# appledore.net
KiCad netlist of a schematic drawn in EasyEDA
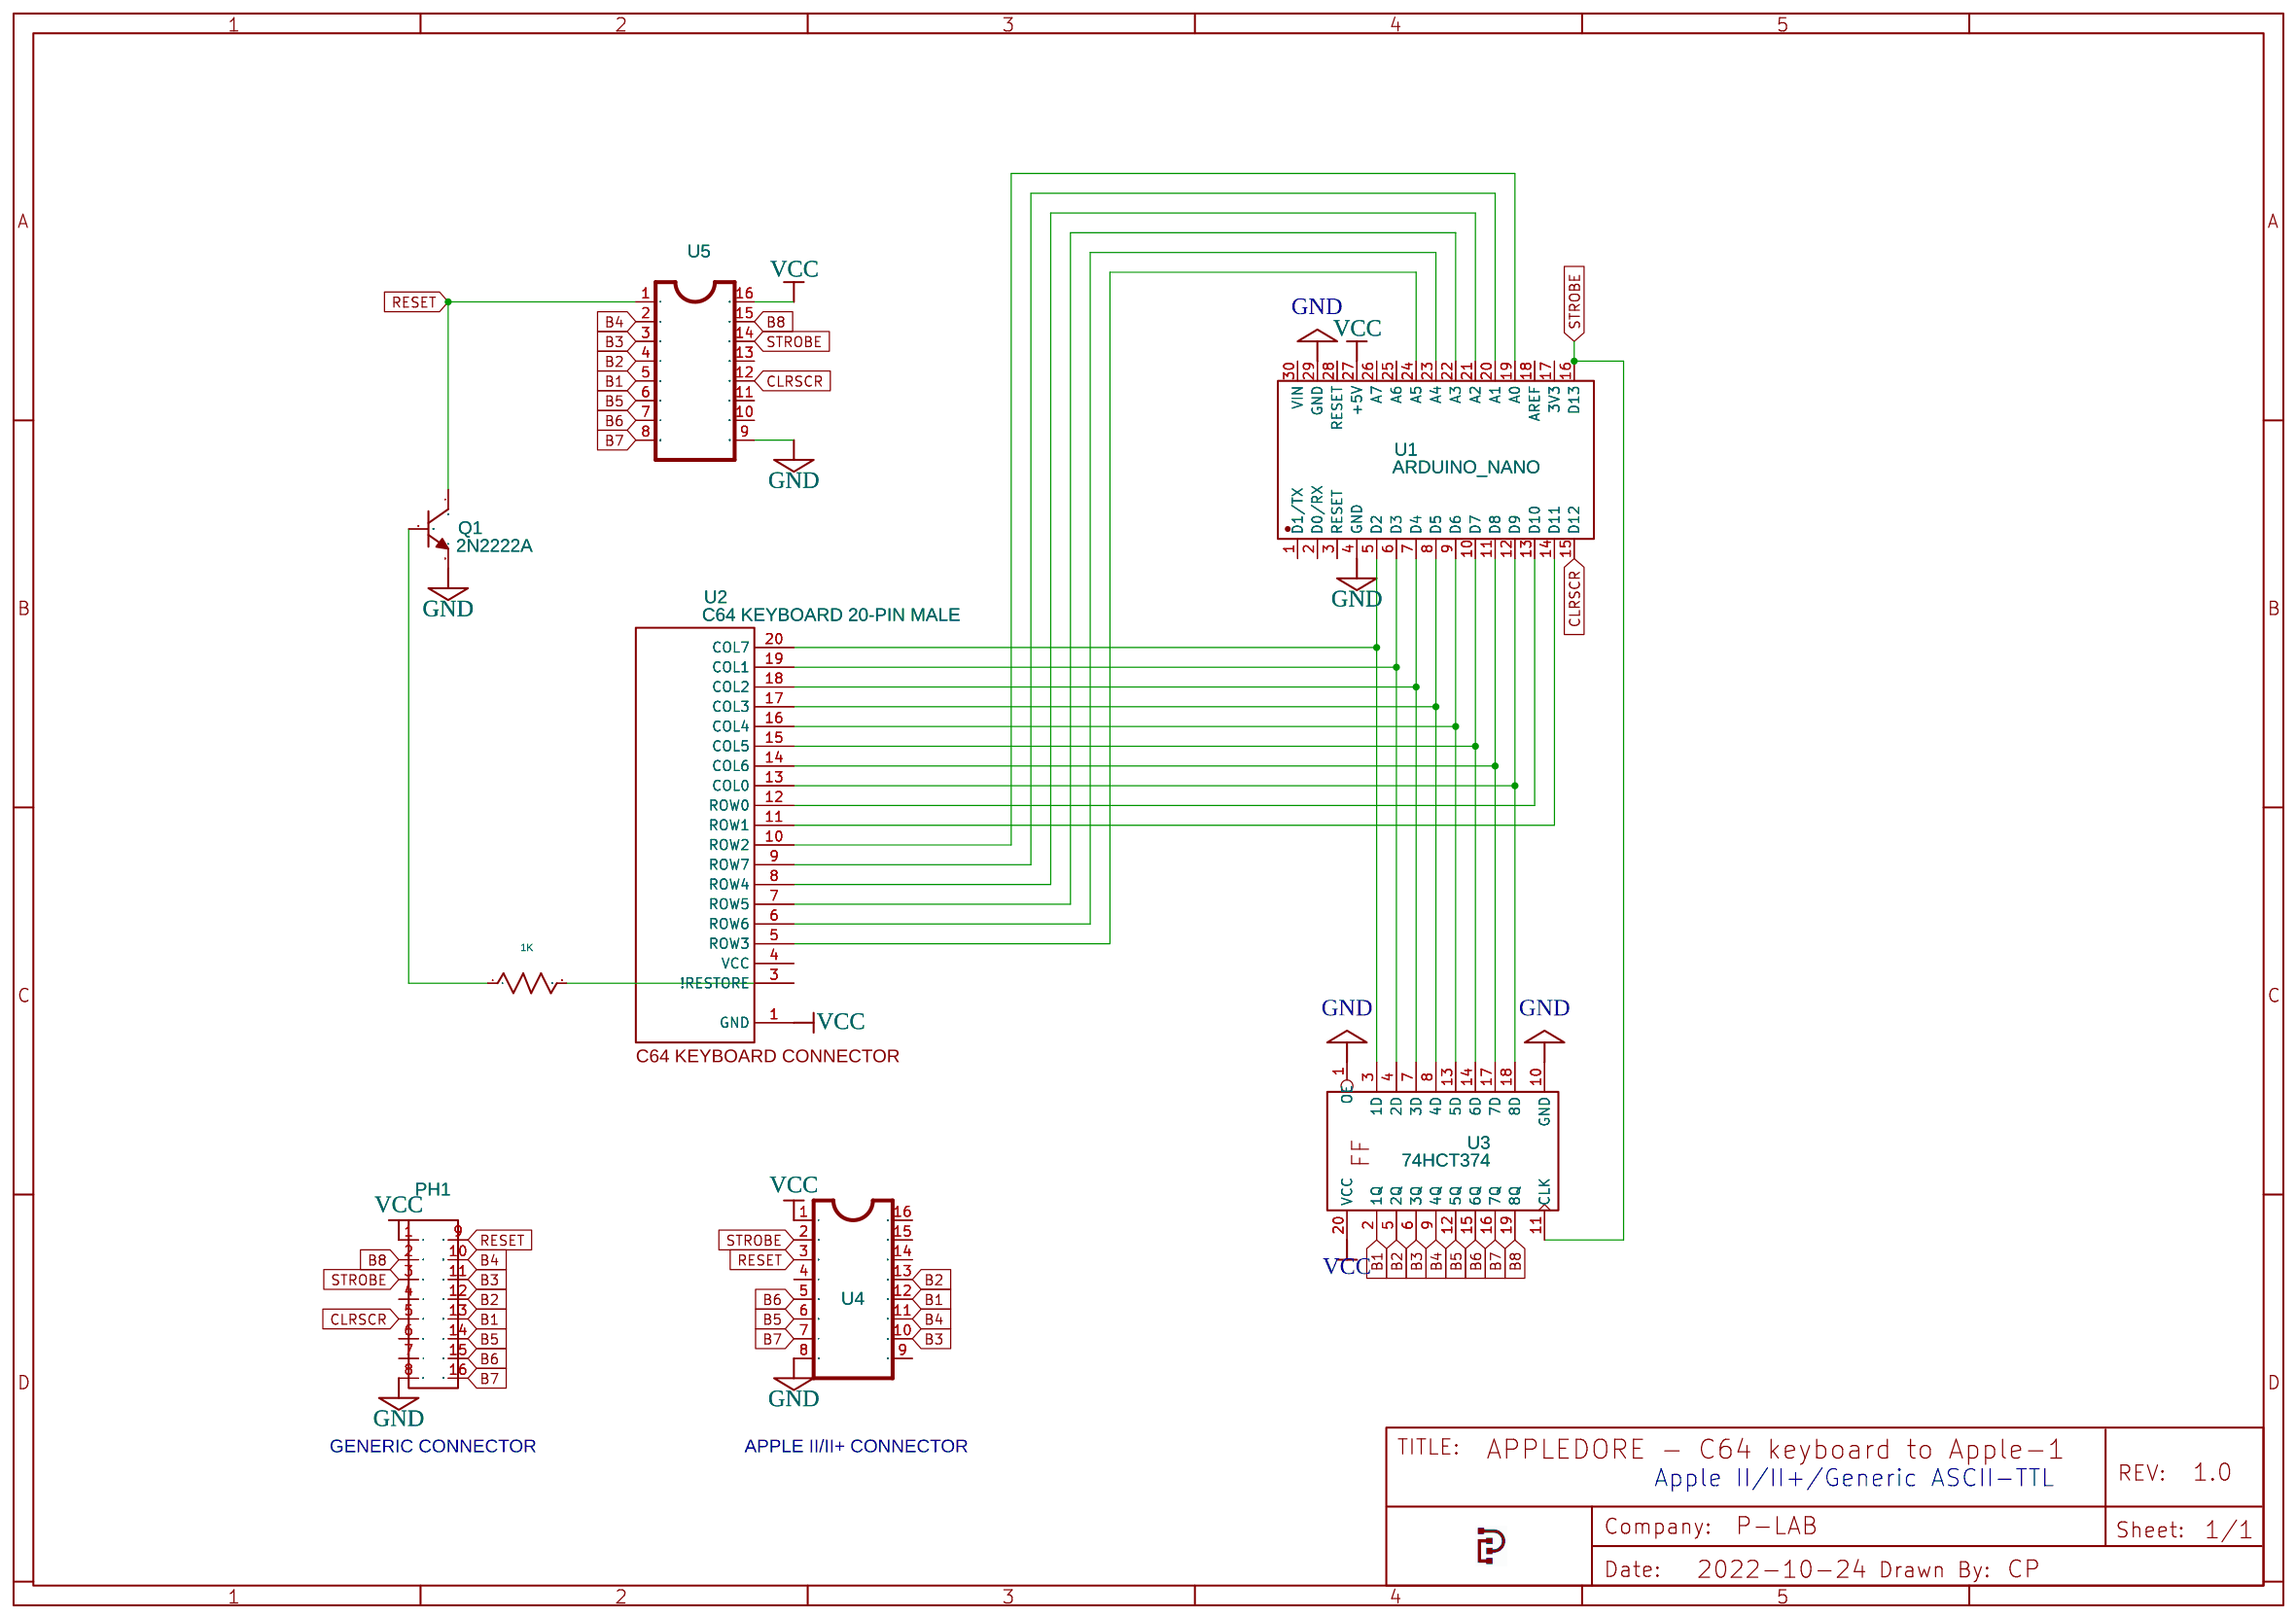
[diagram p0: schematic sheet]

(export (version "E")
  (design (tool "Eeschema 10.0.6"))
  (components
    (comp (ref "1K") (value "1/4W RESISTOR") (libsource (lib "") (part "1/4W RESISTOR")))
    (comp (ref "PH1")
      (value "pinheader08x2")
      (fields (field (name "BOM_Manufacturer Part") "Header 6x1"))
      (libsource (lib "") (part "pinheader08x2"))
    )
    (comp (ref "Q1")
      (value "2N2222A")
      (fields (field (name "BOM_Supplier Part") "C358533"))
      (libsource (lib "") (part "2N2222A"))
    )
    (comp (ref "U1")
      (value "ARDUINO_NANO")
      (fields (field (name "BOM_Supplier Part") "C9900017879"))
      (libsource (lib "") (part "ARDUINO_NANO"))
    )
    (comp (ref "U2")
      (value "C64 KEYBOARD 20-PIN MALE")
      (libsource (lib "") (part "C64 KEYBOARD 20-PIN MALE"))
    )
    (comp (ref "U3") (value "74HCT374") (libsource (lib "") (part "74HCT374")))
    (comp (ref "U4") (value "IC_DIL16-DIP16") (libsource (lib "") (part "IC_DIL16-DIP16")))
    (comp (ref "U5") (value "IC_DIL16-DIP16") (libsource (lib "") (part "IC_DIL16-DIP16")))
  )
  (nets
    (net (code "1") (name "B1") (class "Default")
      (node (ref "PH1") (pin "13") (pinfunction "13_13") (pintype "unspecified"))
      (node (ref "U3") (pin "2") (pinfunction "1Q_2") (pintype "unspecified"))
      (node (ref "U4") (pin "12") (pinfunction "12_12") (pintype "unspecified"))
      (node (ref "U5") (pin "5") (pinfunction "5_5") (pintype "unspecified"))
    )
    (net (code "2") (name "B2") (class "Default")
      (node (ref "PH1") (pin "12") (pinfunction "12_12") (pintype "unspecified"))
      (node (ref "U3") (pin "5") (pinfunction "2Q_5") (pintype "unspecified"))
      (node (ref "U4") (pin "13") (pinfunction "13_13") (pintype "unspecified"))
      (node (ref "U5") (pin "4") (pinfunction "4_4") (pintype "unspecified"))
    )
    (net (code "3") (name "B3") (class "Default")
      (node (ref "PH1") (pin "11") (pinfunction "11_11") (pintype "unspecified"))
      (node (ref "U3") (pin "6") (pinfunction "3Q_6") (pintype "unspecified"))
      (node (ref "U4") (pin "10") (pinfunction "10_10") (pintype "unspecified"))
      (node (ref "U5") (pin "3") (pinfunction "3_3") (pintype "unspecified"))
    )
    (net (code "4") (name "B4") (class "Default")
      (node (ref "PH1") (pin "10") (pinfunction "10_10") (pintype "unspecified"))
      (node (ref "U3") (pin "9") (pinfunction "4Q_9") (pintype "unspecified"))
      (node (ref "U4") (pin "11") (pinfunction "11_11") (pintype "unspecified"))
      (node (ref "U5") (pin "2") (pinfunction "2_2") (pintype "unspecified"))
    )
    (net (code "5") (name "B5") (class "Default")
      (node (ref "PH1") (pin "14") (pinfunction "14_14") (pintype "unspecified"))
      (node (ref "U3") (pin "12") (pinfunction "5Q_12") (pintype "unspecified"))
      (node (ref "U4") (pin "6") (pinfunction "6_6") (pintype "unspecified"))
      (node (ref "U5") (pin "6") (pinfunction "6_6") (pintype "unspecified"))
    )
    (net (code "6") (name "B6") (class "Default")
      (node (ref "PH1") (pin "15") (pinfunction "15_15") (pintype "unspecified"))
      (node (ref "U3") (pin "15") (pinfunction "6Q_15") (pintype "unspecified"))
      (node (ref "U4") (pin "5") (pinfunction "5_5") (pintype "unspecified"))
      (node (ref "U5") (pin "7") (pinfunction "7_7") (pintype "unspecified"))
    )
    (net (code "7") (name "B7") (class "Default")
      (node (ref "PH1") (pin "16") (pinfunction "16_16") (pintype "unspecified"))
      (node (ref "U3") (pin "16") (pinfunction "7Q_16") (pintype "unspecified"))
      (node (ref "U4") (pin "7") (pinfunction "7_7") (pintype "unspecified"))
      (node (ref "U5") (pin "8") (pinfunction "8_8") (pintype "unspecified"))
    )
    (net (code "8") (name "B8") (class "Default")
      (node (ref "PH1") (pin "2") (pinfunction "2_2") (pintype "unspecified"))
      (node (ref "U3") (pin "19") (pinfunction "8Q_19") (pintype "unspecified"))
      (node (ref "U5") (pin "15") (pinfunction "15_15") (pintype "unspecified"))
    )
    (net (code "9") (name "CLRSCR") (class "Default")
      (node (ref "PH1") (pin "5") (pinfunction "5_5") (pintype "unspecified"))
      (node (ref "U1") (pin "15") (pinfunction "D12_15") (pintype "unspecified"))
      (node (ref "U5") (pin "12") (pinfunction "12_12") (pintype "unspecified"))
    )
    (net (code "10") (name "GND") (class "Default")
      (node (ref "PH1") (pin "8") (pinfunction "8_8") (pintype "unspecified"))
      (node (ref "Q1") (pin "3") (pinfunction "E_3") (pintype "unspecified"))
      (node (ref "U1") (pin "29") (pinfunction "GND_29") (pintype "unspecified"))
      (node (ref "U1") (pin "4") (pinfunction "GND_4") (pintype "unspecified"))
      (node (ref "U3") (pin "1") (pinfunction "OE_1") (pintype "unspecified"))
      (node (ref "U3") (pin "10") (pinfunction "GND_10") (pintype "unspecified"))
      (node (ref "U4") (pin "8") (pinfunction "8_8") (pintype "unspecified"))
      (node (ref "U5") (pin "9") (pinfunction "9_9") (pintype "unspecified"))
    )
    (net (code "11") (name "Net-(Q1-B)") (class "Default")
      (node (ref "1K") (pin "1") (pinfunction "1_1") (pintype "unspecified"))
      (node (ref "Q1") (pin "2") (pinfunction "B_2") (pintype "unspecified"))
    )
    (net (code "12") (name "Net-(U1-A0)") (class "Default")
      (node (ref "U1") (pin "19") (pinfunction "A0_19") (pintype "unspecified"))
      (node (ref "U2") (pin "10") (pinfunction "ROW2_10") (pintype "unspecified"))
    )
    (net (code "13") (name "Net-(U1-A1)") (class "Default")
      (node (ref "U1") (pin "20") (pinfunction "A1_20") (pintype "unspecified"))
      (node (ref "U2") (pin "9") (pinfunction "ROW7_9") (pintype "unspecified"))
    )
    (net (code "14") (name "Net-(U1-A2)") (class "Default")
      (node (ref "U1") (pin "21") (pinfunction "A2_21") (pintype "unspecified"))
      (node (ref "U2") (pin "8") (pinfunction "ROW4_8") (pintype "unspecified"))
    )
    (net (code "15") (name "Net-(U1-A3)") (class "Default")
      (node (ref "U1") (pin "22") (pinfunction "A3_22") (pintype "unspecified"))
      (node (ref "U2") (pin "7") (pinfunction "ROW5_7") (pintype "unspecified"))
    )
    (net (code "16") (name "Net-(U1-A4)") (class "Default")
      (node (ref "U1") (pin "23") (pinfunction "A4_23") (pintype "unspecified"))
      (node (ref "U2") (pin "6") (pinfunction "ROW6_6") (pintype "unspecified"))
    )
    (net (code "17") (name "Net-(U1-A5)") (class "Default")
      (node (ref "U1") (pin "24") (pinfunction "A5_24") (pintype "unspecified"))
      (node (ref "U2") (pin "5") (pinfunction "ROW3_5") (pintype "unspecified"))
    )
    (net (code "18") (name "Net-(U1-D2)") (class "Default")
      (node (ref "U1") (pin "5") (pinfunction "D2_5") (pintype "unspecified"))
      (node (ref "U2") (pin "20") (pinfunction "COL7_20") (pintype "unspecified"))
      (node (ref "U3") (pin "3") (pinfunction "1D_3") (pintype "unspecified"))
    )
    (net (code "19") (name "Net-(U1-D3)") (class "Default")
      (node (ref "U1") (pin "6") (pinfunction "D3_6") (pintype "unspecified"))
      (node (ref "U2") (pin "19") (pinfunction "COL1_19") (pintype "unspecified"))
      (node (ref "U3") (pin "4") (pinfunction "2D_4") (pintype "unspecified"))
    )
    (net (code "20") (name "Net-(U1-D4)") (class "Default")
      (node (ref "U1") (pin "7") (pinfunction "D4_7") (pintype "unspecified"))
      (node (ref "U2") (pin "18") (pinfunction "COL2_18") (pintype "unspecified"))
      (node (ref "U3") (pin "7") (pinfunction "3D_7") (pintype "unspecified"))
    )
    (net (code "21") (name "Net-(U1-D5)") (class "Default")
      (node (ref "U1") (pin "8") (pinfunction "D5_8") (pintype "unspecified"))
      (node (ref "U2") (pin "17") (pinfunction "COL3_17") (pintype "unspecified"))
      (node (ref "U3") (pin "8") (pinfunction "4D_8") (pintype "unspecified"))
    )
    (net (code "22") (name "Net-(U1-D6)") (class "Default")
      (node (ref "U1") (pin "9") (pinfunction "D6_9") (pintype "unspecified"))
      (node (ref "U2") (pin "16") (pinfunction "COL4_16") (pintype "unspecified"))
      (node (ref "U3") (pin "13") (pinfunction "5D_13") (pintype "unspecified"))
    )
    (net (code "23") (name "Net-(U1-D7)") (class "Default")
      (node (ref "U1") (pin "10") (pinfunction "D7_10") (pintype "unspecified"))
      (node (ref "U2") (pin "15") (pinfunction "COL5_15") (pintype "unspecified"))
      (node (ref "U3") (pin "14") (pinfunction "6D_14") (pintype "unspecified"))
    )
    (net (code "24") (name "Net-(U1-D8)") (class "Default")
      (node (ref "U1") (pin "11") (pinfunction "D8_11") (pintype "unspecified"))
      (node (ref "U2") (pin "14") (pinfunction "COL6_14") (pintype "unspecified"))
      (node (ref "U3") (pin "17") (pinfunction "7D_17") (pintype "unspecified"))
    )
    (net (code "25") (name "Net-(U1-D9)") (class "Default")
      (node (ref "U1") (pin "12") (pinfunction "D9_12") (pintype "unspecified"))
      (node (ref "U2") (pin "13") (pinfunction "COL0_13") (pintype "unspecified"))
      (node (ref "U3") (pin "18") (pinfunction "8D_18") (pintype "unspecified"))
    )
    (net (code "26") (name "Net-(U1-D10)") (class "Default")
      (node (ref "U1") (pin "13") (pinfunction "D10_13") (pintype "unspecified"))
      (node (ref "U2") (pin "12") (pinfunction "ROW0_12") (pintype "unspecified"))
    )
    (net (code "27") (name "Net-(U1-D11)") (class "Default")
      (node (ref "U1") (pin "14") (pinfunction "D11_14") (pintype "unspecified"))
      (node (ref "U2") (pin "11") (pinfunction "ROW1_11") (pintype "unspecified"))
    )
    (net (code "28") (name "Net-(U2-!RESTORE)") (class "Default")
      (node (ref "1K") (pin "2") (pinfunction "2_2") (pintype "unspecified"))
      (node (ref "U2") (pin "3") (pinfunction "!RESTORE_3") (pintype "unspecified"))
    )
    (net (code "29") (name "RESET") (class "Default")
      (node (ref "PH1") (pin "9") (pinfunction "9_9") (pintype "unspecified"))
      (node (ref "Q1") (pin "1") (pinfunction "C_1") (pintype "unspecified"))
      (node (ref "U4") (pin "3") (pinfunction "3_3") (pintype "unspecified"))
      (node (ref "U5") (pin "1") (pinfunction "1_1") (pintype "unspecified"))
    )
    (net (code "30") (name "STROBE") (class "Default")
      (node (ref "PH1") (pin "3") (pinfunction "3_3") (pintype "unspecified"))
      (node (ref "U1") (pin "16") (pinfunction "D13_16") (pintype "unspecified"))
      (node (ref "U3") (pin "11") (pinfunction "CLK_11") (pintype "unspecified"))
      (node (ref "U4") (pin "2") (pinfunction "2_2") (pintype "unspecified"))
      (node (ref "U5") (pin "14") (pinfunction "14_14") (pintype "unspecified"))
    )
    (net (code "31") (name "VCC") (class "Default")
      (node (ref "PH1") (pin "1") (pinfunction "1_1") (pintype "unspecified"))
      (node (ref "U1") (pin "27") (pinfunction "+5V_27") (pintype "unspecified"))
      (node (ref "U2") (pin "1") (pinfunction "GND_1") (pintype "unspecified"))
      (node (ref "U3") (pin "20") (pinfunction "VCC_20") (pintype "unspecified"))
      (node (ref "U4") (pin "1") (pinfunction "1_1") (pintype "unspecified"))
      (node (ref "U5") (pin "16") (pinfunction "16_16") (pintype "unspecified"))
    )
    (net (code "32") (name "unconnected-(PH1-Pad4)") (class "Default")
      (node (ref "PH1") (pin "4") (pinfunction "4_4") (pintype "unspecified"))
    )
    (net (code "33") (name "unconnected-(PH1-Pad6)") (class "Default")
      (node (ref "PH1") (pin "6") (pinfunction "6_6") (pintype "unspecified"))
    )
    (net (code "34") (name "unconnected-(PH1-Pad7)") (class "Default")
      (node (ref "PH1") (pin "7") (pinfunction "7_7") (pintype "unspecified"))
    )
    (net (code "35") (name "unconnected-(U1-3V3-Pad17)") (class "Default")
      (node (ref "U1") (pin "17") (pinfunction "3V3_17") (pintype "unspecified"))
    )
    (net (code "36") (name "unconnected-(U1-A6-Pad25)") (class "Default")
      (node (ref "U1") (pin "25") (pinfunction "A6_25") (pintype "unspecified"))
    )
    (net (code "37") (name "unconnected-(U1-A7-Pad26)") (class "Default")
      (node (ref "U1") (pin "26") (pinfunction "A7_26") (pintype "unspecified"))
    )
    (net (code "38") (name "unconnected-(U1-AREF-Pad18)") (class "Default")
      (node (ref "U1") (pin "18") (pinfunction "AREF_18") (pintype "unspecified"))
    )
    (net (code "39") (name "unconnected-(U1-D0{slash}RX-Pad2)") (class "Default")
      (node (ref "U1") (pin "2") (pinfunction "D0/RX_2") (pintype "unspecified"))
    )
    (net (code "40") (name "unconnected-(U1-D1{slash}TX-Pad1)") (class "Default")
      (node (ref "U1") (pin "1") (pinfunction "D1/TX_1") (pintype "unspecified"))
    )
    (net (code "41") (name "unconnected-(U1-RESET-Pad3)") (class "Default")
      (node (ref "U1") (pin "3") (pinfunction "RESET_3") (pintype "unspecified"))
    )
    (net (code "42") (name "unconnected-(U1-RESET-Pad28)") (class "Default")
      (node (ref "U1") (pin "28") (pinfunction "RESET_28") (pintype "unspecified"))
    )
    (net (code "43") (name "unconnected-(U1-VIN-Pad30)") (class "Default")
      (node (ref "U1") (pin "30") (pinfunction "VIN_30") (pintype "unspecified"))
    )
    (net (code "44") (name "unconnected-(U2-VCC-Pad4)") (class "Default")
      (node (ref "U2") (pin "4") (pinfunction "VCC_4") (pintype "unspecified"))
    )
    (net (code "45") (name "unconnected-(U4-Pad4)") (class "Default")
      (node (ref "U4") (pin "4") (pinfunction "4_4") (pintype "unspecified"))
    )
    (net (code "46") (name "unconnected-(U4-Pad9)") (class "Default")
      (node (ref "U4") (pin "9") (pinfunction "9_9") (pintype "unspecified"))
    )
    (net (code "47") (name "unconnected-(U4-Pad14)") (class "Default")
      (node (ref "U4") (pin "14") (pinfunction "14_14") (pintype "unspecified"))
    )
    (net (code "48") (name "unconnected-(U4-Pad15)") (class "Default")
      (node (ref "U4") (pin "15") (pinfunction "15_15") (pintype "unspecified"))
    )
    (net (code "49") (name "unconnected-(U4-Pad16)") (class "Default")
      (node (ref "U4") (pin "16") (pinfunction "16_16") (pintype "unspecified"))
    )
    (net (code "50") (name "unconnected-(U5-Pad10)") (class "Default")
      (node (ref "U5") (pin "10") (pinfunction "10_10") (pintype "unspecified"))
    )
    (net (code "51") (name "unconnected-(U5-Pad11)") (class "Default")
      (node (ref "U5") (pin "11") (pinfunction "11_11") (pintype "unspecified"))
    )
    (net (code "52") (name "unconnected-(U5-Pad13)") (class "Default")
      (node (ref "U5") (pin "13") (pinfunction "13_13") (pintype "unspecified"))
    )
  )
)
